# HC-SR04_Middle-Man_v9.net
KiCad netlist of a schematic drawn in EAGLE
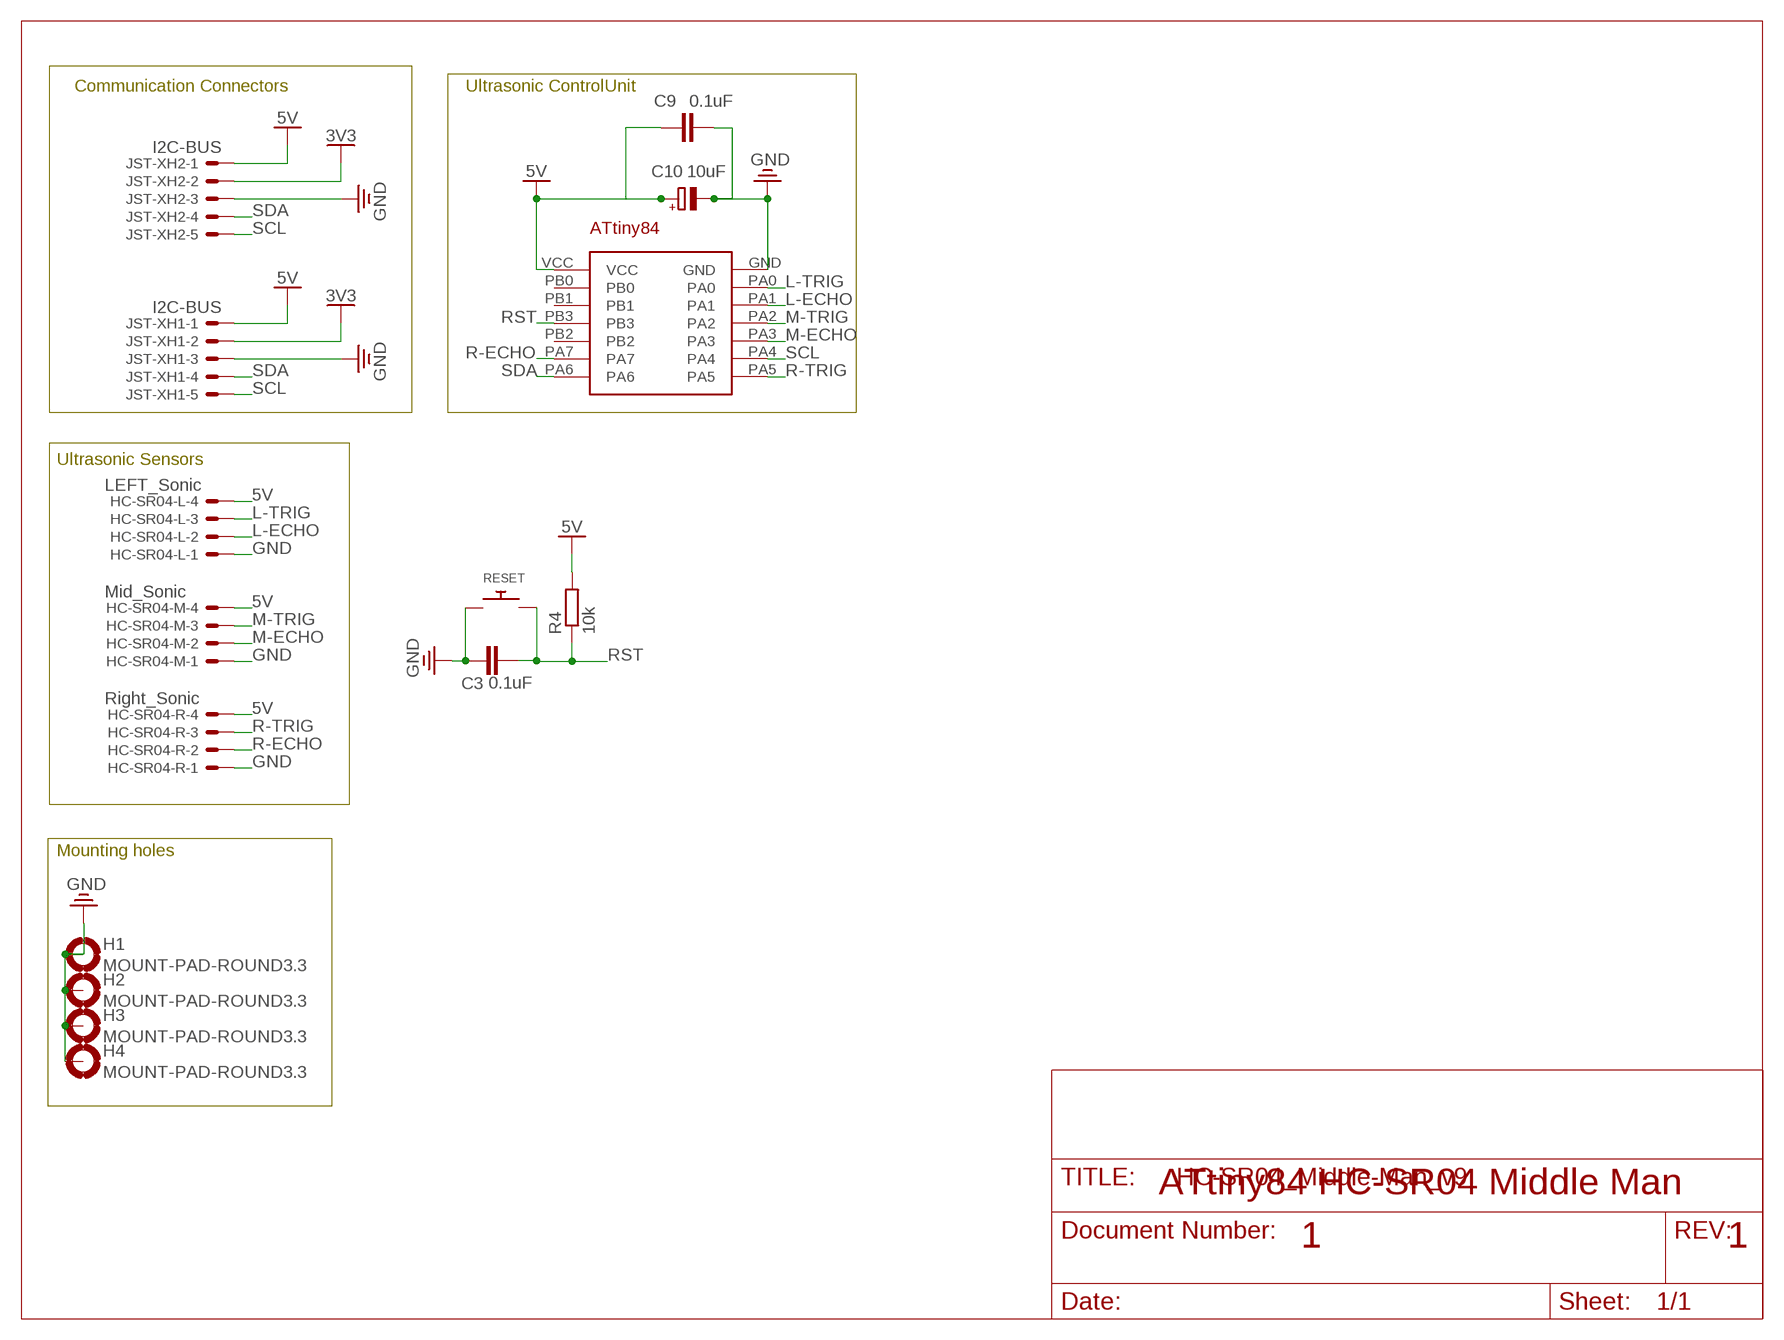
[diagram p0: schematic, sheet 1]

(export (version "E")
  (design (tool "Eeschema 10.0.6"))
  (components
    (comp (ref "C3")
      (value "0.1uF")
      (footprint "eagle-import:C025-030X050")
      (libsource (lib "eagle-import") (part "C-EU025-030X050"))
    )
    (comp (ref "C9")
      (value "0.1uF")
      (footprint "eagle-import:C025-025X050")
      (libsource (lib "eagle-import") (part "C-EU025-025X050"))
    )
    (comp (ref "C10")
      (value "10uF")
      (footprint "eagle-import:E5-10,5")
      (libsource (lib "eagle-import") (part "CPOL-EUE5-10.5"))
    )
    (comp (ref "H1")
      (value "MOUNT-PAD-ROUND3.3")
      (footprint "eagle-import:3,3-PAD")
      (libsource (lib "eagle-import") (part "MOUNT-PAD-ROUND3.3"))
    )
    (comp (ref "H2")
      (value "MOUNT-PAD-ROUND3.3")
      (footprint "eagle-import:3,3-PAD")
      (libsource (lib "eagle-import") (part "MOUNT-PAD-ROUND3.3"))
    )
    (comp (ref "H3")
      (value "MOUNT-PAD-ROUND3.3")
      (footprint "eagle-import:3,3-PAD")
      (libsource (lib "eagle-import") (part "MOUNT-PAD-ROUND3.3"))
    )
    (comp (ref "H4")
      (value "MOUNT-PAD-ROUND3.3")
      (footprint "eagle-import:3,3-PAD")
      (libsource (lib "eagle-import") (part "MOUNT-PAD-ROUND3.3"))
    )
    (comp (ref "HC-SR04-L")
      (value "LEFT_Sonic")
      (footprint "eagle-import:JST-XH-04-PACKAGE-LONG-PAD")
      (libsource (lib "eagle-import") (part "JST-XH-04-PIN-LONG-PAD"))
    )
    (comp (ref "HC-SR04-M")
      (value "Mid_Sonic")
      (footprint "eagle-import:JST-XH-04-PACKAGE-LONG-PAD")
      (libsource (lib "eagle-import") (part "JST-XH-04-PIN-LONG-PAD"))
    )
    (comp (ref "HC-SR04-R")
      (value "Right_Sonic")
      (footprint "eagle-import:JST-XH-04-PACKAGE-LONG-PAD")
      (libsource (lib "eagle-import") (part "JST-XH-04-PIN-LONG-PAD"))
    )
    (comp (ref "JST-XH1")
      (value "I2C-BUS")
      (footprint "eagle-import:JST-XH-05-PACKAGE-LONG-PAD")
      (libsource (lib "eagle-import") (part "JST-XH-05-PIN-LONG-PAD"))
    )
    (comp (ref "JST-XH2")
      (value "I2C-BUS")
      (footprint "eagle-import:JST-XH-05-PACKAGE-LONG-PAD")
      (libsource (lib "eagle-import") (part "JST-XH-05-PIN-LONG-PAD"))
    )
    (comp (ref "R4")
      (value "10k")
      (footprint "eagle-import:0204_7")
      (libsource (lib "eagle-import") (part "R-EU_0204/7"))
    )
    (comp (ref "RESET")
      (value "SWITCH_PUSHBUTTONEVQ-PE")
      (footprint "eagle-import:TACT_PANA-EVQ")
      (libsource (lib "eagle-import") (part "SWITCH_PUSHBUTTONEVQ-PE"))
    )
    (comp (ref "U$3")
      (value "ATTINY84DIP")
      (footprint "eagle-import:ATTINY84(DIP)")
      (libsource (lib "eagle-import") (part "ATTINY84DIP"))
    )
  )
  (nets
    (net (code "1") (name "/L-ECHO") (class "Default")
      (node (ref "HC-SR04-L") (pin "2") (pinfunction "S_2") (pintype "passive"))
      (node (ref "U$3") (pin "PA1") (pinfunction "PA1_PA1") (pintype "bidirectional"))
    )
    (net (code "2") (name "/L-TRIG") (class "Default")
      (node (ref "HC-SR04-L") (pin "3") (pinfunction "S_3") (pintype "passive"))
      (node (ref "U$3") (pin "PA0") (pinfunction "PA0_PA0") (pintype "bidirectional"))
    )
    (net (code "3") (name "/M-ECHO") (class "Default")
      (node (ref "HC-SR04-M") (pin "2") (pinfunction "S_2") (pintype "passive"))
      (node (ref "U$3") (pin "PA3") (pinfunction "PA3_PA3") (pintype "bidirectional"))
    )
    (net (code "4") (name "/M-TRIG") (class "Default")
      (node (ref "HC-SR04-M") (pin "3") (pinfunction "S_3") (pintype "passive"))
      (node (ref "U$3") (pin "PA2") (pinfunction "PA2_PA2") (pintype "bidirectional"))
    )
    (net (code "5") (name "/R-ECHO") (class "Default")
      (node (ref "HC-SR04-R") (pin "2") (pinfunction "S_2") (pintype "passive"))
      (node (ref "U$3") (pin "PA7") (pinfunction "PA7_PA7") (pintype "bidirectional"))
    )
    (net (code "6") (name "/R-TRIG") (class "Default")
      (node (ref "HC-SR04-R") (pin "3") (pinfunction "S_3") (pintype "passive"))
      (node (ref "U$3") (pin "PA5") (pinfunction "PA5_PA5") (pintype "bidirectional"))
    )
    (net (code "7") (name "/RST") (class "Default")
      (node (ref "C3") (pin "2") (pinfunction "2_2") (pintype "passive"))
      (node (ref "R4") (pin "1") (pinfunction "1_1") (pintype "passive"))
      (node (ref "RESET") (pin "P$2") (pinfunction "P$2_P$2") (pintype "passive"))
      (node (ref "U$3") (pin "PB3") (pinfunction "PB3_PB3") (pintype "bidirectional"))
    )
    (net (code "8") (name "/SCL") (class "Default")
      (node (ref "JST-XH1") (pin "5") (pinfunction "S_5") (pintype "passive"))
      (node (ref "JST-XH2") (pin "5") (pinfunction "S_5") (pintype "passive"))
      (node (ref "U$3") (pin "PA4") (pinfunction "PA4_PA4") (pintype "bidirectional"))
    )
    (net (code "9") (name "/SDA") (class "Default")
      (node (ref "JST-XH1") (pin "4") (pinfunction "S_4") (pintype "passive"))
      (node (ref "JST-XH2") (pin "4") (pinfunction "S_4") (pintype "passive"))
      (node (ref "U$3") (pin "PA6") (pinfunction "PA6_PA6") (pintype "bidirectional"))
    )
    (net (code "10") (name "3V3") (class "Default")
      (node (ref "JST-XH1") (pin "2") (pinfunction "S_2") (pintype "passive"))
      (node (ref "JST-XH2") (pin "2") (pinfunction "S_2") (pintype "passive"))
    )
    (net (code "11") (name "5V") (class "Default")
      (node (ref "C10") (pin "+") (pinfunction "+_+") (pintype "passive"))
      (node (ref "C9") (pin "1") (pinfunction "1_1") (pintype "passive"))
      (node (ref "HC-SR04-L") (pin "4") (pinfunction "S_4") (pintype "passive"))
      (node (ref "HC-SR04-M") (pin "4") (pinfunction "S_4") (pintype "passive"))
      (node (ref "HC-SR04-R") (pin "4") (pinfunction "S_4") (pintype "passive"))
      (node (ref "JST-XH1") (pin "1") (pinfunction "S_1") (pintype "passive"))
      (node (ref "JST-XH2") (pin "1") (pinfunction "S_1") (pintype "passive"))
      (node (ref "R4") (pin "2") (pinfunction "2_2") (pintype "passive"))
      (node (ref "U$3") (pin "VCC") (pinfunction "VCC_VCC") (pintype "bidirectional"))
    )
    (net (code "12") (name "GND") (class "Default")
      (node (ref "C10") (pin "-") (pinfunction "-_-") (pintype "passive"))
      (node (ref "C3") (pin "1") (pinfunction "1_1") (pintype "passive"))
      (node (ref "C9") (pin "2") (pinfunction "2_2") (pintype "passive"))
      (node (ref "H1") (pin "B3,3") (pinfunction "MOUNT_B3,3") (pintype "passive"))
      (node (ref "H2") (pin "B3,3") (pinfunction "MOUNT_B3,3") (pintype "passive"))
      (node (ref "H3") (pin "B3,3") (pinfunction "MOUNT_B3,3") (pintype "passive"))
      (node (ref "H4") (pin "B3,3") (pinfunction "MOUNT_B3,3") (pintype "passive"))
      (node (ref "HC-SR04-L") (pin "1") (pinfunction "S_1") (pintype "passive"))
      (node (ref "HC-SR04-M") (pin "1") (pinfunction "S_1") (pintype "passive"))
      (node (ref "HC-SR04-R") (pin "1") (pinfunction "S_1") (pintype "passive"))
      (node (ref "JST-XH1") (pin "3") (pinfunction "S_3") (pintype "passive"))
      (node (ref "JST-XH2") (pin "3") (pinfunction "S_3") (pintype "passive"))
      (node (ref "RESET") (pin "P$1") (pinfunction "P$1_P$1") (pintype "passive"))
      (node (ref "U$3") (pin "GND") (pinfunction "GND_GND") (pintype "bidirectional"))
    )
    (net (code "13") (name "unconnected-(U$3-PadPB0)") (class "Default")
      (node (ref "U$3") (pin "PB0") (pinfunction "PB0_PB0") (pintype "bidirectional"))
    )
    (net (code "14") (name "unconnected-(U$3-PadPB1)") (class "Default")
      (node (ref "U$3") (pin "PB1") (pinfunction "PB1_PB1") (pintype "bidirectional"))
    )
    (net (code "15") (name "unconnected-(U$3-PadPB2)") (class "Default")
      (node (ref "U$3") (pin "PB2") (pinfunction "PB2_PB2") (pintype "bidirectional"))
    )
  )
)
